# G1000_Cessna_Main.net
KiCad netlist of a schematic drawn in EasyEDA
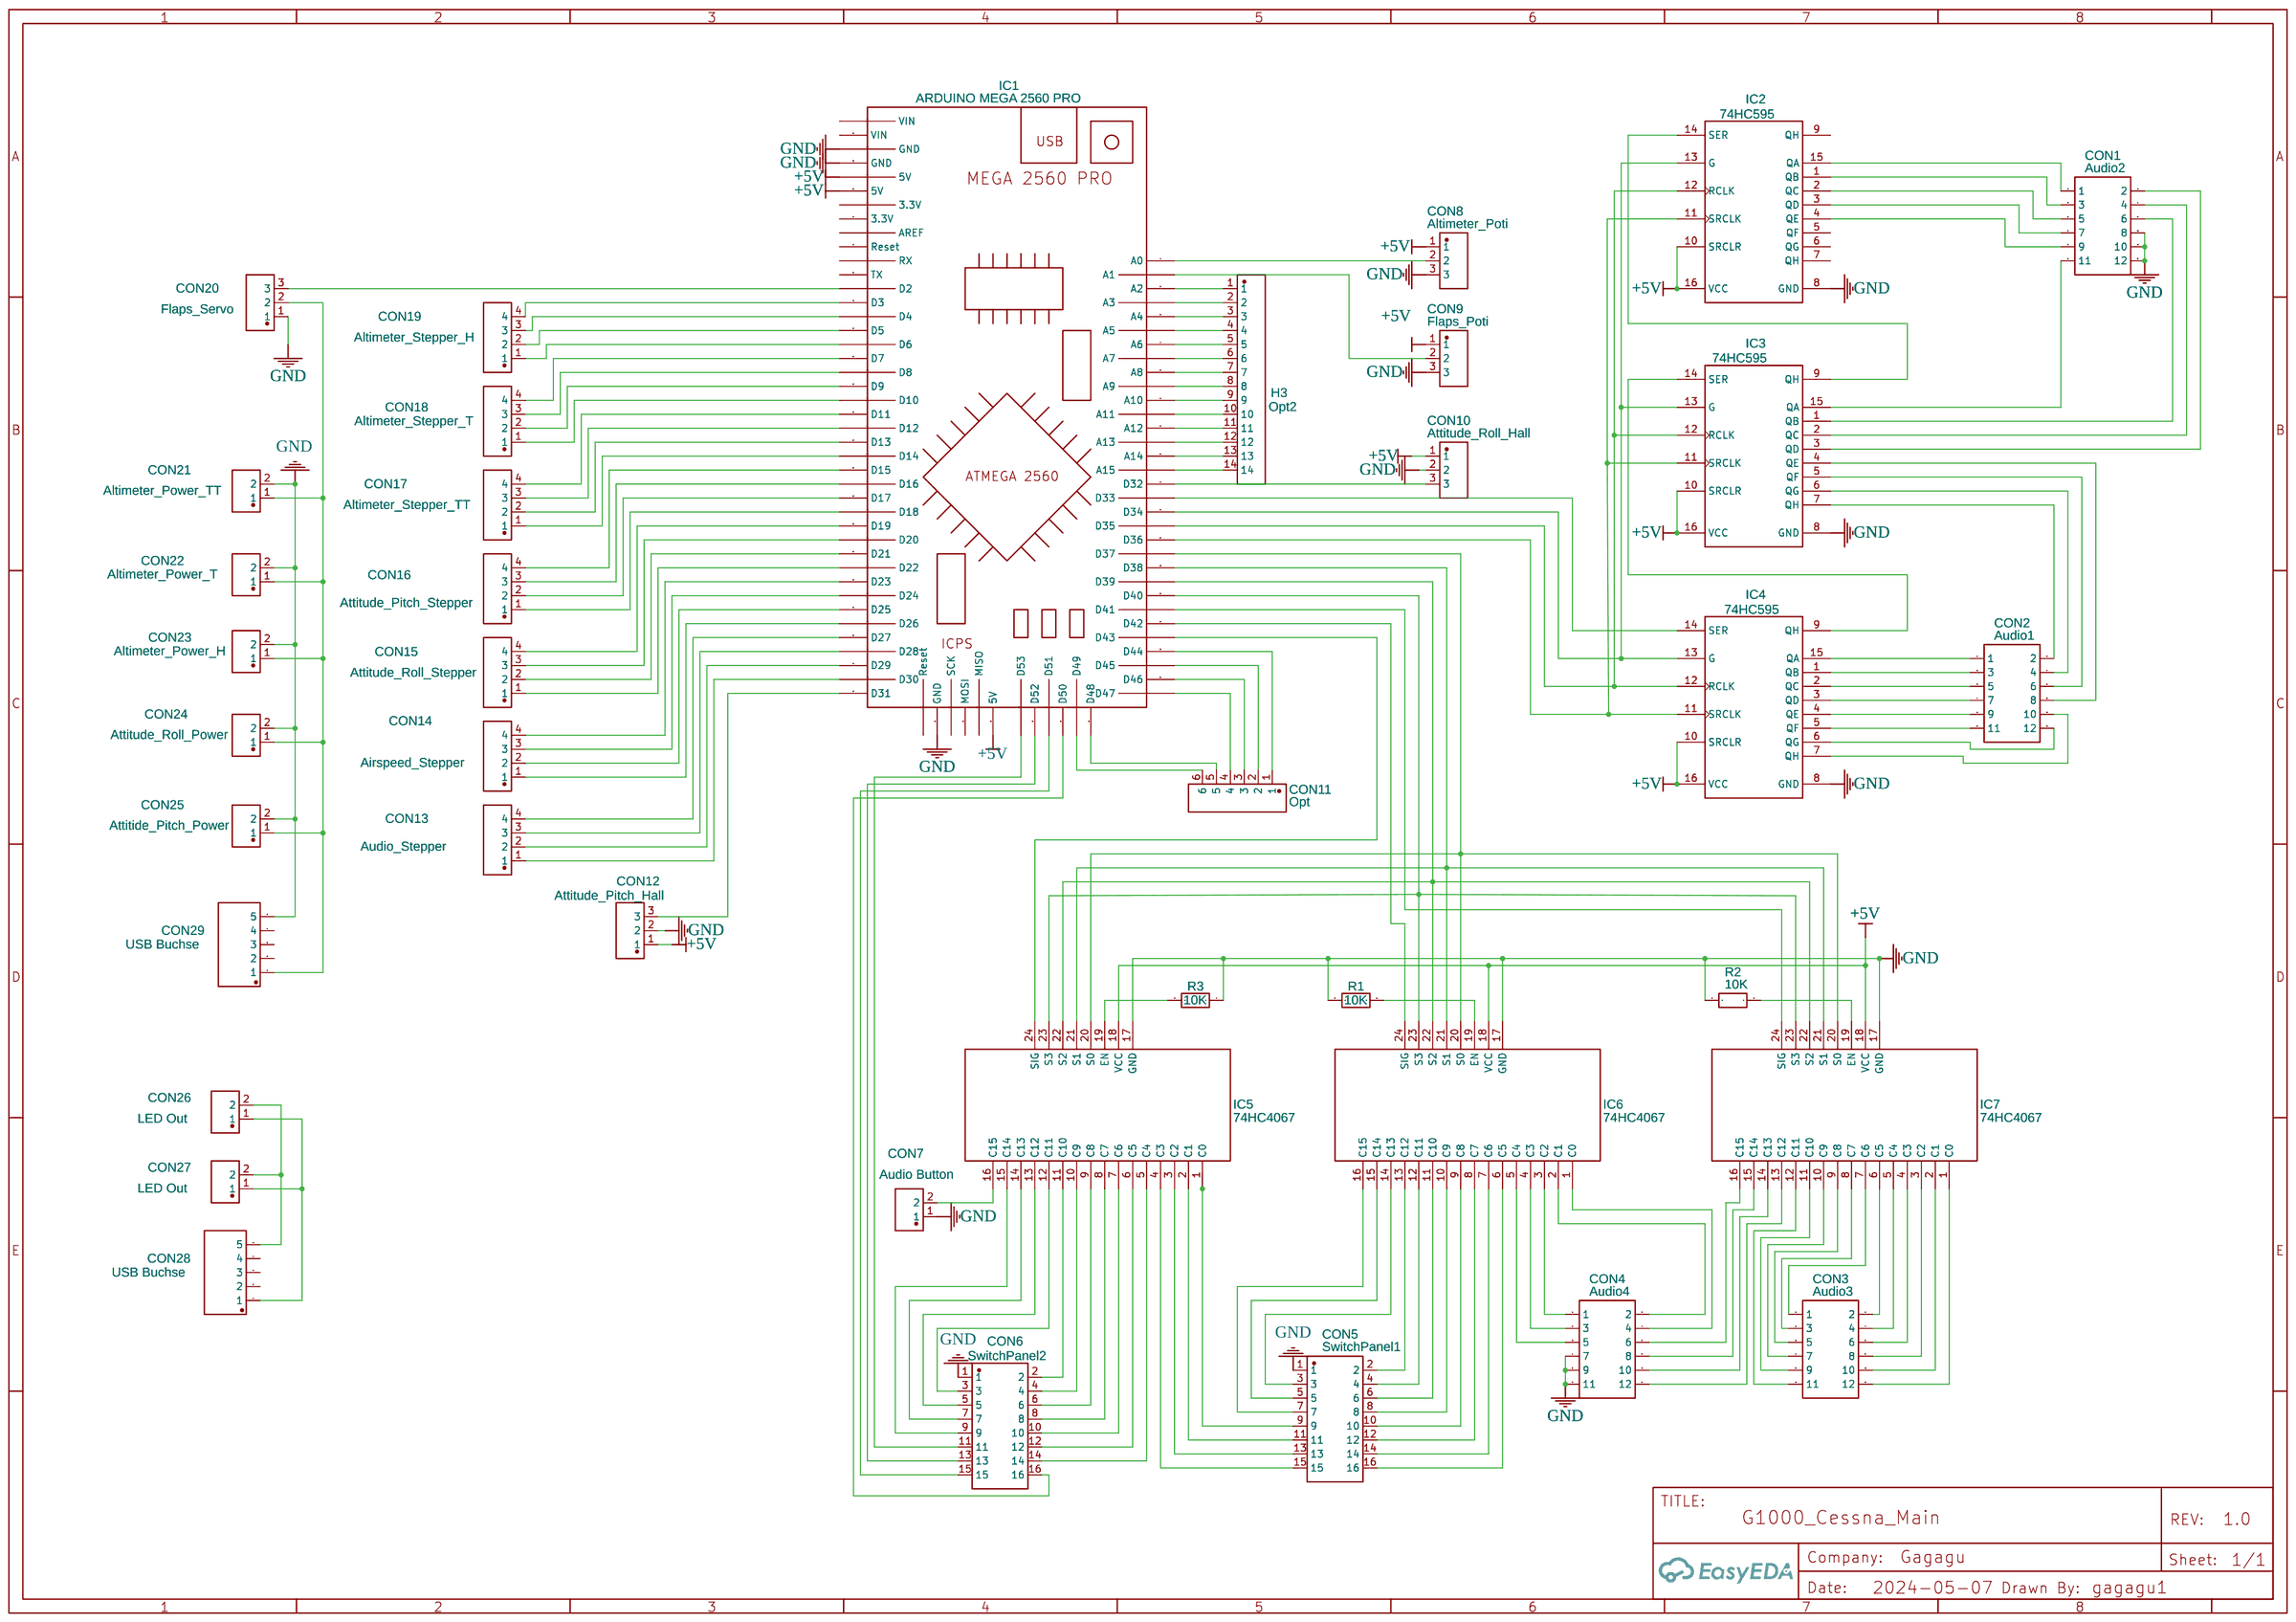
[diagram p0: schematic sheet]

(export (version "E")
  (design (tool "Eeschema 10.0.6"))
  (components
    (comp (ref "CON1")
      (value "Audio2")
      (fields (field (name "Manufacturer Part") "2.54-2*6P简牛") (field (name "Manufacturer") "BOOMELE(博穆精密)"))
      (libsource (lib "") (part "SOCKET HDR-IDC-2.54-2X6P"))
    )
    (comp (ref "CON2")
      (value "Audio1")
      (fields (field (name "Manufacturer Part") "2.54-2*6P简牛") (field (name "Manufacturer") "BOOMELE(博穆精密)"))
      (libsource (lib "") (part "SOCKET HDR-IDC-2.54-2X6P"))
    )
    (comp (ref "CON3")
      (value "Audio3")
      (fields (field (name "Manufacturer Part") "2.54-2*6P简牛") (field (name "Manufacturer") "BOOMELE(博穆精密)"))
      (libsource (lib "") (part "SOCKET HDR-IDC-2.54-2X6P"))
    )
    (comp (ref "CON4")
      (value "Audio4")
      (fields (field (name "Manufacturer Part") "2.54-2*6P简牛") (field (name "Manufacturer") "BOOMELE(博穆精密)"))
      (libsource (lib "") (part "SOCKET HDR-IDC-2.54-2X6P"))
    )
    (comp (ref "CON5")
      (value "SwitchPanel1")
      (fields
        (field (name "Manufacturer Part") "KH-2.54PH180-2X8P-L8.9")
        (field (name "Manufacturer") "kinghelm(金航标)")
      )
      (libsource (lib "") (part "KH-2.54PH180-2X8P-L8.9"))
    )
    (comp (ref "CON6")
      (value "SwitchPanel2")
      (fields
        (field (name "Manufacturer Part") "KH-2.54PH180-2X8P-L8.9")
        (field (name "Manufacturer") "kinghelm(金航标)")
      )
      (libsource (lib "") (part "KH-2.54PH180-2X8P-L8.9"))
    )
    (comp (ref "CON7")
      (value "Audio Button")
      (fields (field (name "Manufacturer Part") "HC-XH-2A-G") (field (name "Manufacturer") "HCTL(华灿天禄)"))
      (libsource (lib "") (part "HC-XH-2A-G"))
    )
    (comp (ref "CON8")
      (value "Altimeter_Poti")
      (fields (field (name "Manufacturer Part") "HC-XH-3A-G") (field (name "Manufacturer") "HCTL(华灿天禄)"))
      (libsource (lib "") (part "HC-XH-3A-G"))
    )
    (comp (ref "CON9")
      (value "Flaps_Poti")
      (fields (field (name "Manufacturer Part") "HC-XH-3A-G") (field (name "Manufacturer") "HCTL(华灿天禄)"))
      (libsource (lib "") (part "HC-XH-3A-G"))
    )
    (comp (ref "CON10")
      (value "Attitude_Roll_Hall")
      (fields (field (name "Manufacturer Part") "HC-XH-3A-G") (field (name "Manufacturer") "HCTL(华灿天禄)"))
      (libsource (lib "") (part "HC-XH-3A-G"))
    )
    (comp (ref "CON11")
      (value "Opt")
      (fields (field (name "Manufacturer Part") "XH-6A") (field (name "Manufacturer") "CAX"))
      (libsource (lib "") (part "ARUN-CONN-TH_XH-6A"))
    )
    (comp (ref "CON12")
      (value "Attitude_Pitch_Hall")
      (fields (field (name "Manufacturer Part") "HC-XH-3A-G") (field (name "Manufacturer") "HCTL(华灿天禄)"))
      (libsource (lib "") (part "HC-XH-3A-G_1"))
    )
    (comp (ref "CON13")
      (value "Audio_Stepper")
      (fields (field (name "Manufacturer Part") "XH-4A绿色") (field (name "Manufacturer") "BOOMELE(博穆精密)"))
      (libsource (lib "") (part "ARUN-CONN-TH_XH-4A"))
    )
    (comp (ref "CON14")
      (value "Airspeed_Stepper")
      (fields (field (name "Manufacturer Part") "XH-4A绿色") (field (name "Manufacturer") "BOOMELE(博穆精密)"))
      (libsource (lib "") (part "ARUN-CONN-TH_XH-4A"))
    )
    (comp (ref "CON15")
      (value "Attitude_Roll_Stepper")
      (fields (field (name "Manufacturer Part") "XH-4A绿色") (field (name "Manufacturer") "BOOMELE(博穆精密)"))
      (libsource (lib "") (part "ARUN-CONN-TH_XH-4A"))
    )
    (comp (ref "CON16")
      (value "Attitude_Pitch_Stepper")
      (fields (field (name "Manufacturer Part") "XH-4A绿色") (field (name "Manufacturer") "BOOMELE(博穆精密)"))
      (libsource (lib "") (part "ARUN-CONN-TH_XH-4A"))
    )
    (comp (ref "CON17")
      (value "Altimeter_Stepper_TT")
      (fields (field (name "Manufacturer Part") "XH-4A绿色") (field (name "Manufacturer") "BOOMELE(博穆精密)"))
      (libsource (lib "") (part "ARUN-CONN-TH_XH-4A"))
    )
    (comp (ref "CON18")
      (value "Altimeter_Stepper_T")
      (fields (field (name "Manufacturer Part") "XH-4A绿色") (field (name "Manufacturer") "BOOMELE(博穆精密)"))
      (libsource (lib "") (part "ARUN-CONN-TH_XH-4A"))
    )
    (comp (ref "CON19")
      (value "Altimeter_Stepper_H")
      (fields (field (name "Manufacturer Part") "XH-4A绿色") (field (name "Manufacturer") "BOOMELE(博穆精密)"))
      (libsource (lib "") (part "ARUN-CONN-TH_XH-4A"))
    )
    (comp (ref "CON20")
      (value "Flaps_Servo")
      (fields (field (name "Manufacturer Part") "HC-XH-3A-G") (field (name "Manufacturer") "HCTL(华灿天禄)"))
      (libsource (lib "") (part "HC-XH-3A-G_1"))
    )
    (comp (ref "CON21")
      (value "Altimeter_Power_TT")
      (fields (field (name "Manufacturer Part") "HC-XH-2A-G") (field (name "Manufacturer") "HCTL(华灿天禄)"))
      (libsource (lib "") (part "HC-XH-2A-G"))
    )
    (comp (ref "CON22")
      (value "Altimeter_Power_T")
      (fields (field (name "Manufacturer Part") "HC-XH-2A-G") (field (name "Manufacturer") "HCTL(华灿天禄)"))
      (libsource (lib "") (part "HC-XH-2A-G"))
    )
    (comp (ref "CON23")
      (value "Altimeter_Power_H")
      (fields (field (name "Manufacturer Part") "HC-XH-2A-G") (field (name "Manufacturer") "HCTL(华灿天禄)"))
      (libsource (lib "") (part "HC-XH-2A-G"))
    )
    (comp (ref "CON24")
      (value "Attitude_Roll_Power")
      (fields (field (name "Manufacturer Part") "HC-XH-2A-G") (field (name "Manufacturer") "HCTL(华灿天禄)"))
      (libsource (lib "") (part "HC-XH-2A-G"))
    )
    (comp (ref "CON25")
      (value "Attitide_Pitch_Power")
      (fields (field (name "Manufacturer Part") "HC-XH-2A-G") (field (name "Manufacturer") "HCTL(华灿天禄)"))
      (libsource (lib "") (part "HC-XH-2A-G"))
    )
    (comp (ref "CON26")
      (value "LED Out")
      (fields (field (name "Manufacturer Part") "HC-XH-2A-G") (field (name "Manufacturer") "HCTL(华灿天禄)"))
      (libsource (lib "") (part "HC-XH-2A-G"))
    )
    (comp (ref "CON27")
      (value "LED Out")
      (fields (field (name "Manufacturer Part") "HC-XH-2A-G") (field (name "Manufacturer") "HCTL(华灿天禄)"))
      (libsource (lib "") (part "HC-XH-2A-G"))
    )
    (comp (ref "CON28")
      (value "USB Buchse")
      (fields
        (field (name "Manufacturer Part") "210S-1*5P L=11.6MMGold-plated black")
        (field (name "Manufacturer") "Ckmtw")
      )
      (libsource (lib "") (part "Battery Pack Connector"))
    )
    (comp (ref "CON29")
      (value "USB Buchse")
      (fields
        (field (name "Manufacturer Part") "210S-1*5P L=11.6MMGold-plated black")
        (field (name "Manufacturer") "Ckmtw")
      )
      (libsource (lib "") (part "Battery Pack Connector"))
    )
    (comp (ref "H3")
      (value "Opt2")
      (fields
        (field (name "Manufacturer Part") "KH-1.27PH180-1X14P-L7.2")
        (field (name "Manufacturer") "kinghelm(金航标)")
      )
      (libsource (lib "") (part "KH-1.27PH180-1X14P-L7.2"))
    )
    (comp (ref "IC1")
      (value "ARDUINO MEGA 2560 PRO")
      (fields (field (name "Manufacturer Part") "Arduino Mega 2560 Pro Mini"))
      (libsource (lib "") (part "ARDUINO MEGA 2560 PRO_2020"))
    )
    (comp (ref "IC2") (value "74HC595") (libsource (lib "") (part "SN74HC595N_DIP")))
    (comp (ref "IC3") (value "74HC595") (libsource (lib "") (part "SN74HC595N_DIP")))
    (comp (ref "IC4") (value "74HC595") (libsource (lib "") (part "SN74HC595N_DIP")))
    (comp (ref "IC5") (value "74HC4067") (libsource (lib "") (part "CD74HC4067")))
    (comp (ref "IC6") (value "74HC4067") (libsource (lib "") (part "CD74HC4067")))
    (comp (ref "IC7") (value "74HC4067") (libsource (lib "") (part "CD74HC4067")))
    (comp (ref "R1") (value "10K") (libsource (lib "") (part "R_AXIAL-0.4_EU")))
    (comp (ref "R2") (value "10K") (libsource (lib "") (part "R_AXIAL-0.4_EU_1")))
    (comp (ref "R3") (value "10K") (libsource (lib "") (part "R_AXIAL-0.4_EU")))
  )
  (nets
    (net (code "1") (name "+5V") (class "Default")
      (node (ref "CON10") (pin "1") (pinfunction "1_1") (pintype "unspecified"))
      (node (ref "CON12") (pin "1") (pinfunction "1_1") (pintype "unspecified"))
      (node (ref "CON8") (pin "1") (pinfunction "1_1") (pintype "unspecified"))
      (node (ref "CON9") (pin "1") (pinfunction "1_1") (pintype "unspecified"))
      (node (ref "IC1") (pin "39") (pinfunction "5V_39") (pintype "unspecified"))
      (node (ref "IC1") (pin "81") (pinfunction "5V_81") (pintype "unspecified"))
      (node (ref "IC1") (pin "82") (pinfunction "5V_82") (pintype "unspecified"))
      (node (ref "IC2") (pin "10") (pinfunction "SRCLR_10") (pintype "unspecified"))
      (node (ref "IC2") (pin "16") (pinfunction "VCC_16") (pintype "passive"))
      (node (ref "IC3") (pin "10") (pinfunction "SRCLR_10") (pintype "unspecified"))
      (node (ref "IC3") (pin "16") (pinfunction "VCC_16") (pintype "passive"))
      (node (ref "IC4") (pin "10") (pinfunction "SRCLR_10") (pintype "unspecified"))
      (node (ref "IC4") (pin "16") (pinfunction "VCC_16") (pintype "passive"))
      (node (ref "IC5") (pin "18") (pinfunction "VCC_18") (pintype "unspecified"))
      (node (ref "IC6") (pin "18") (pinfunction "VCC_18") (pintype "unspecified"))
      (node (ref "IC7") (pin "18") (pinfunction "VCC_18") (pintype "unspecified"))
    )
    (net (code "2") (name "GND") (class "Default")
      (node (ref "CON1") (pin "10") (pinfunction "10_10") (pintype "unspecified"))
      (node (ref "CON1") (pin "12") (pinfunction "12_12") (pintype "unspecified"))
      (node (ref "CON1") (pin "8") (pinfunction "8_8") (pintype "unspecified"))
      (node (ref "CON10") (pin "2") (pinfunction "2_2") (pintype "unspecified"))
      (node (ref "CON12") (pin "2") (pinfunction "2_2") (pintype "unspecified"))
      (node (ref "CON20") (pin "1") (pinfunction "1_1") (pintype "unspecified"))
      (node (ref "CON21") (pin "2") (pinfunction "2_2") (pintype "unspecified"))
      (node (ref "CON22") (pin "2") (pinfunction "2_2") (pintype "unspecified"))
      (node (ref "CON23") (pin "2") (pinfunction "2_2") (pintype "unspecified"))
      (node (ref "CON24") (pin "2") (pinfunction "2_2") (pintype "unspecified"))
      (node (ref "CON25") (pin "2") (pinfunction "2_2") (pintype "unspecified"))
      (node (ref "CON29") (pin "5") (pinfunction "5_5") (pintype "unspecified"))
      (node (ref "CON4") (pin "11") (pinfunction "11_11") (pintype "unspecified"))
      (node (ref "CON4") (pin "7") (pinfunction "7_7") (pintype "unspecified"))
      (node (ref "CON4") (pin "9") (pinfunction "9_9") (pintype "unspecified"))
      (node (ref "CON5") (pin "1") (pinfunction "1_1") (pintype "unspecified"))
      (node (ref "CON6") (pin "1") (pinfunction "1_1") (pintype "unspecified"))
      (node (ref "CON7") (pin "1") (pinfunction "1_1") (pintype "unspecified"))
      (node (ref "CON8") (pin "3") (pinfunction "3_3") (pintype "unspecified"))
      (node (ref "CON9") (pin "3") (pinfunction "3_3") (pintype "unspecified"))
      (node (ref "IC1") (pin "43") (pinfunction "GND_43") (pintype "unspecified"))
      (node (ref "IC1") (pin "83") (pinfunction "GND_83") (pintype "unspecified"))
      (node (ref "IC1") (pin "84") (pinfunction "GND_84") (pintype "unspecified"))
      (node (ref "IC2") (pin "8") (pinfunction "GND_8") (pintype "passive"))
      (node (ref "IC3") (pin "8") (pinfunction "GND_8") (pintype "passive"))
      (node (ref "IC4") (pin "8") (pinfunction "GND_8") (pintype "passive"))
      (node (ref "IC5") (pin "17") (pinfunction "GND_17") (pintype "unspecified"))
      (node (ref "IC6") (pin "17") (pinfunction "GND_17") (pintype "unspecified"))
      (node (ref "IC7") (pin "17") (pinfunction "GND_17") (pintype "unspecified"))
      (node (ref "R1") (pin "2") (pinfunction "2_2") (pintype "unspecified"))
      (node (ref "R2") (pin "1") (pinfunction "1_1") (pintype "unspecified"))
      (node (ref "R3") (pin "1") (pinfunction "1_1") (pintype "unspecified"))
    )
    (net (code "3") (name "Net-(CON2-Pad2)") (class "Default")
      (node (ref "CON2") (pin "2") (pinfunction "2_2") (pintype "unspecified"))
      (node (ref "IC3") (pin "7") (pinfunction "QH_7") (pintype "unspecified"))
    )
    (net (code "4") (name "Net-(CON2-Pad10)") (class "Default")
      (node (ref "CON2") (pin "10") (pinfunction "10_10") (pintype "unspecified"))
      (node (ref "IC4") (pin "7") (pinfunction "QH_7") (pintype "unspecified"))
    )
    (net (code "5") (name "Net-(CON20-Pad2)") (class "Default")
      (node (ref "CON20") (pin "2") (pinfunction "2_2") (pintype "unspecified"))
      (node (ref "CON21") (pin "1") (pinfunction "1_1") (pintype "unspecified"))
      (node (ref "CON22") (pin "1") (pinfunction "1_1") (pintype "unspecified"))
      (node (ref "CON23") (pin "1") (pinfunction "1_1") (pintype "unspecified"))
      (node (ref "CON24") (pin "1") (pinfunction "1_1") (pintype "unspecified"))
      (node (ref "CON25") (pin "1") (pinfunction "1_1") (pintype "unspecified"))
      (node (ref "CON29") (pin "1") (pinfunction "1_1") (pintype "unspecified"))
    )
    (net (code "6") (name "Net-(CON26-Pad1)") (class "Default")
      (node (ref "CON26") (pin "1") (pinfunction "1_1") (pintype "unspecified"))
      (node (ref "CON27") (pin "1") (pinfunction "1_1") (pintype "unspecified"))
      (node (ref "CON28") (pin "1") (pinfunction "1_1") (pintype "unspecified"))
    )
    (net (code "7") (name "Net-(CON26-Pad2)") (class "Default")
      (node (ref "CON26") (pin "2") (pinfunction "2_2") (pintype "unspecified"))
      (node (ref "CON27") (pin "2") (pinfunction "2_2") (pintype "unspecified"))
      (node (ref "CON28") (pin "5") (pinfunction "5_5") (pintype "unspecified"))
    )
    (net (code "8") (name "Net-(IC1-A0)") (class "Default")
      (node (ref "CON8") (pin "2") (pinfunction "2_2") (pintype "unspecified"))
      (node (ref "IC1") (pin "1") (pinfunction "A0_1") (pintype "unspecified"))
    )
    (net (code "9") (name "Net-(IC1-A1)") (class "Default")
      (node (ref "CON9") (pin "2") (pinfunction "2_2") (pintype "unspecified"))
      (node (ref "IC1") (pin "2") (pinfunction "A1_2") (pintype "unspecified"))
    )
    (net (code "10") (name "Net-(IC1-A2)") (class "Default")
      (node (ref "H3") (pin "1") (pinfunction "1_1") (pintype "unspecified"))
      (node (ref "IC1") (pin "3") (pinfunction "A2_3") (pintype "unspecified"))
    )
    (net (code "11") (name "Net-(IC1-A3)") (class "Default")
      (node (ref "H3") (pin "2") (pinfunction "2_2") (pintype "unspecified"))
      (node (ref "IC1") (pin "4") (pinfunction "A3_4") (pintype "unspecified"))
    )
    (net (code "12") (name "Net-(IC1-A4)") (class "Default")
      (node (ref "H3") (pin "3") (pinfunction "3_3") (pintype "unspecified"))
      (node (ref "IC1") (pin "5") (pinfunction "A4_5") (pintype "unspecified"))
    )
    (net (code "13") (name "Net-(IC1-A5)") (class "Default")
      (node (ref "H3") (pin "4") (pinfunction "4_4") (pintype "unspecified"))
      (node (ref "IC1") (pin "6") (pinfunction "A5_6") (pintype "unspecified"))
    )
    (net (code "14") (name "Net-(IC1-A6)") (class "Default")
      (node (ref "H3") (pin "5") (pinfunction "5_5") (pintype "unspecified"))
      (node (ref "IC1") (pin "7") (pinfunction "A6_7") (pintype "unspecified"))
    )
    (net (code "15") (name "Net-(IC1-A7)") (class "Default")
      (node (ref "H3") (pin "6") (pinfunction "6_6") (pintype "unspecified"))
      (node (ref "IC1") (pin "8") (pinfunction "A7_8") (pintype "unspecified"))
    )
    (net (code "16") (name "Net-(IC1-A8)") (class "Default")
      (node (ref "H3") (pin "7") (pinfunction "7_7") (pintype "unspecified"))
      (node (ref "IC1") (pin "9") (pinfunction "A8_9") (pintype "unspecified"))
    )
    (net (code "17") (name "Net-(IC1-A9)") (class "Default")
      (node (ref "H3") (pin "8") (pinfunction "8_8") (pintype "unspecified"))
      (node (ref "IC1") (pin "10") (pinfunction "A9_10") (pintype "unspecified"))
    )
    (net (code "18") (name "Net-(IC1-A10)") (class "Default")
      (node (ref "H3") (pin "9") (pinfunction "9_9") (pintype "unspecified"))
      (node (ref "IC1") (pin "11") (pinfunction "A10_11") (pintype "unspecified"))
    )
    (net (code "19") (name "Net-(IC1-A11)") (class "Default")
      (node (ref "H3") (pin "10") (pinfunction "10_10") (pintype "unspecified"))
      (node (ref "IC1") (pin "12") (pinfunction "A11_12") (pintype "unspecified"))
    )
    (net (code "20") (name "Net-(IC1-A12)") (class "Default")
      (node (ref "H3") (pin "11") (pinfunction "11_11") (pintype "unspecified"))
      (node (ref "IC1") (pin "13") (pinfunction "A12_13") (pintype "unspecified"))
    )
    (net (code "21") (name "Net-(IC1-A13)") (class "Default")
      (node (ref "H3") (pin "12") (pinfunction "12_12") (pintype "unspecified"))
      (node (ref "IC1") (pin "14") (pinfunction "A13_14") (pintype "unspecified"))
    )
    (net (code "22") (name "Net-(IC1-A14)") (class "Default")
      (node (ref "H3") (pin "13") (pinfunction "13_13") (pintype "unspecified"))
      (node (ref "IC1") (pin "15") (pinfunction "A14_15") (pintype "unspecified"))
    )
    (net (code "23") (name "Net-(IC1-A15)") (class "Default")
      (node (ref "H3") (pin "14") (pinfunction "14_14") (pintype "unspecified"))
      (node (ref "IC1") (pin "16") (pinfunction "A15_16") (pintype "unspecified"))
    )
    (net (code "24") (name "Net-(IC1-D2)") (class "Default")
      (node (ref "CON20") (pin "3") (pinfunction "3_3") (pintype "unspecified"))
      (node (ref "IC1") (pin "74") (pinfunction "D2_74") (pintype "unspecified"))
    )
    (net (code "25") (name "Net-(IC1-D3)") (class "Default")
      (node (ref "CON19") (pin "4") (pinfunction "4_4") (pintype "unspecified"))
      (node (ref "IC1") (pin "73") (pinfunction "D3_73") (pintype "unspecified"))
    )
    (net (code "26") (name "Net-(IC1-D4)") (class "Default")
      (node (ref "CON19") (pin "3") (pinfunction "3_3") (pintype "unspecified"))
      (node (ref "IC1") (pin "72") (pinfunction "D4_72") (pintype "unspecified"))
    )
    (net (code "27") (name "Net-(IC1-D5)") (class "Default")
      (node (ref "CON19") (pin "2") (pinfunction "2_2") (pintype "unspecified"))
      (node (ref "IC1") (pin "71") (pinfunction "D5_71") (pintype "unspecified"))
    )
    (net (code "28") (name "Net-(IC1-D6)") (class "Default")
      (node (ref "CON19") (pin "1") (pinfunction "1_1") (pintype "unspecified"))
      (node (ref "IC1") (pin "70") (pinfunction "D6_70") (pintype "unspecified"))
    )
    (net (code "29") (name "Net-(IC1-D7)") (class "Default")
      (node (ref "CON18") (pin "4") (pinfunction "4_4") (pintype "unspecified"))
      (node (ref "IC1") (pin "69") (pinfunction "D7_69") (pintype "unspecified"))
    )
    (net (code "30") (name "Net-(IC1-D8)") (class "Default")
      (node (ref "CON18") (pin "3") (pinfunction "3_3") (pintype "unspecified"))
      (node (ref "IC1") (pin "68") (pinfunction "D8_68") (pintype "unspecified"))
    )
    (net (code "31") (name "Net-(IC1-D9)") (class "Default")
      (node (ref "CON18") (pin "2") (pinfunction "2_2") (pintype "unspecified"))
      (node (ref "IC1") (pin "67") (pinfunction "D9_67") (pintype "unspecified"))
    )
    (net (code "32") (name "Net-(IC1-D10)") (class "Default")
      (node (ref "CON18") (pin "1") (pinfunction "1_1") (pintype "unspecified"))
      (node (ref "IC1") (pin "66") (pinfunction "D10_66") (pintype "unspecified"))
    )
    (net (code "33") (name "Net-(IC1-D11)") (class "Default")
      (node (ref "CON17") (pin "4") (pinfunction "4_4") (pintype "unspecified"))
      (node (ref "IC1") (pin "65") (pinfunction "D11_65") (pintype "unspecified"))
    )
    (net (code "34") (name "Net-(IC1-D12)") (class "Default")
      (node (ref "CON17") (pin "3") (pinfunction "3_3") (pintype "unspecified"))
      (node (ref "IC1") (pin "64") (pinfunction "D12_64") (pintype "unspecified"))
    )
    (net (code "35") (name "Net-(IC1-D13)") (class "Default")
      (node (ref "CON17") (pin "2") (pinfunction "2_2") (pintype "unspecified"))
      (node (ref "IC1") (pin "63") (pinfunction "D13_63") (pintype "unspecified"))
    )
    (net (code "36") (name "Net-(IC1-D14)") (class "Default")
      (node (ref "CON17") (pin "1") (pinfunction "1_1") (pintype "unspecified"))
      (node (ref "IC1") (pin "62") (pinfunction "D14_62") (pintype "unspecified"))
    )
    (net (code "37") (name "Net-(IC1-D15)") (class "Default")
      (node (ref "CON16") (pin "4") (pinfunction "4_4") (pintype "unspecified"))
      (node (ref "IC1") (pin "61") (pinfunction "D15_61") (pintype "unspecified"))
    )
    (net (code "38") (name "Net-(IC1-D16)") (class "Default")
      (node (ref "CON16") (pin "3") (pinfunction "3_3") (pintype "unspecified"))
      (node (ref "IC1") (pin "60") (pinfunction "D16_60") (pintype "unspecified"))
    )
    (net (code "39") (name "Net-(IC1-D17)") (class "Default")
      (node (ref "CON16") (pin "2") (pinfunction "2_2") (pintype "unspecified"))
      (node (ref "IC1") (pin "59") (pinfunction "D17_59") (pintype "unspecified"))
    )
    (net (code "40") (name "Net-(IC1-D18)") (class "Default")
      (node (ref "CON16") (pin "1") (pinfunction "1_1") (pintype "unspecified"))
      (node (ref "IC1") (pin "58") (pinfunction "D18_58") (pintype "unspecified"))
    )
    (net (code "41") (name "Net-(IC1-D19)") (class "Default")
      (node (ref "CON15") (pin "4") (pinfunction "4_4") (pintype "unspecified"))
      (node (ref "IC1") (pin "57") (pinfunction "D19_57") (pintype "unspecified"))
    )
    (net (code "42") (name "Net-(IC1-D20)") (class "Default")
      (node (ref "CON15") (pin "3") (pinfunction "3_3") (pintype "unspecified"))
      (node (ref "IC1") (pin "56") (pinfunction "D20_56") (pintype "unspecified"))
    )
    (net (code "43") (name "Net-(IC1-D21)") (class "Default")
      (node (ref "CON15") (pin "2") (pinfunction "2_2") (pintype "unspecified"))
      (node (ref "IC1") (pin "55") (pinfunction "D21_55") (pintype "unspecified"))
    )
    (net (code "44") (name "Net-(IC1-D22)") (class "Default")
      (node (ref "CON15") (pin "1") (pinfunction "1_1") (pintype "unspecified"))
      (node (ref "IC1") (pin "54") (pinfunction "D22_54") (pintype "unspecified"))
    )
    (net (code "45") (name "Net-(IC1-D23)") (class "Default")
      (node (ref "CON14") (pin "4") (pinfunction "4_4") (pintype "unspecified"))
      (node (ref "IC1") (pin "53") (pinfunction "D23_53") (pintype "unspecified"))
    )
    (net (code "46") (name "Net-(IC1-D24)") (class "Default")
      (node (ref "CON14") (pin "3") (pinfunction "3_3") (pintype "unspecified"))
      (node (ref "IC1") (pin "52") (pinfunction "D24_52") (pintype "unspecified"))
    )
    (net (code "47") (name "Net-(IC1-D25)") (class "Default")
      (node (ref "CON14") (pin "2") (pinfunction "2_2") (pintype "unspecified"))
      (node (ref "IC1") (pin "51") (pinfunction "D25_51") (pintype "unspecified"))
    )
    (net (code "48") (name "Net-(IC1-D26)") (class "Default")
      (node (ref "CON14") (pin "1") (pinfunction "1_1") (pintype "unspecified"))
      (node (ref "IC1") (pin "50") (pinfunction "D26_50") (pintype "unspecified"))
    )
    (net (code "49") (name "Net-(IC1-D27)") (class "Default")
      (node (ref "CON13") (pin "4") (pinfunction "4_4") (pintype "unspecified"))
      (node (ref "IC1") (pin "49") (pinfunction "D27_49") (pintype "unspecified"))
    )
    (net (code "50") (name "Net-(IC1-D28)") (class "Default")
      (node (ref "CON13") (pin "3") (pinfunction "3_3") (pintype "unspecified"))
      (node (ref "IC1") (pin "48") (pinfunction "D28_48") (pintype "unspecified"))
    )
    (net (code "51") (name "Net-(IC1-D29)") (class "Default")
      (node (ref "CON13") (pin "2") (pinfunction "2_2") (pintype "unspecified"))
      (node (ref "IC1") (pin "47") (pinfunction "D29_47") (pintype "unspecified"))
    )
    (net (code "52") (name "Net-(IC1-D30)") (class "Default")
      (node (ref "CON13") (pin "1") (pinfunction "1_1") (pintype "unspecified"))
      (node (ref "IC1") (pin "46") (pinfunction "D30_46") (pintype "unspecified"))
    )
    (net (code "53") (name "Net-(IC1-D31)") (class "Default")
      (node (ref "CON12") (pin "3") (pinfunction "3_3") (pintype "unspecified"))
      (node (ref "IC1") (pin "45") (pinfunction "D31_45") (pintype "unspecified"))
    )
    (net (code "54") (name "Net-(IC1-D32)") (class "Default")
      (node (ref "CON10") (pin "3") (pinfunction "3_3") (pintype "unspecified"))
      (node (ref "IC1") (pin "17") (pinfunction "D32_17") (pintype "unspecified"))
    )
    (net (code "55") (name "Net-(IC1-D33)") (class "Default")
      (node (ref "IC1") (pin "18") (pinfunction "D33_18") (pintype "unspecified"))
      (node (ref "IC4") (pin "14") (pinfunction "SER_14") (pintype "unspecified"))
    )
    (net (code "56") (name "Net-(IC1-D34)") (class "Default")
      (node (ref "IC1") (pin "19") (pinfunction "D34_19") (pintype "unspecified"))
      (node (ref "IC2") (pin "13") (pinfunction "G_13") (pintype "unspecified"))
      (node (ref "IC3") (pin "13") (pinfunction "G_13") (pintype "unspecified"))
      (node (ref "IC4") (pin "13") (pinfunction "G_13") (pintype "unspecified"))
    )
    (net (code "57") (name "Net-(IC1-D35)") (class "Default")
      (node (ref "IC1") (pin "20") (pinfunction "D35_20") (pintype "unspecified"))
      (node (ref "IC2") (pin "12") (pinfunction "RCLK_12") (pintype "unspecified"))
      (node (ref "IC3") (pin "12") (pinfunction "RCLK_12") (pintype "unspecified"))
      (node (ref "IC4") (pin "12") (pinfunction "RCLK_12") (pintype "unspecified"))
    )
    (net (code "58") (name "Net-(IC1-D36)") (class "Default")
      (node (ref "IC1") (pin "21") (pinfunction "D36_21") (pintype "unspecified"))
      (node (ref "IC2") (pin "11") (pinfunction "SRCLK_11") (pintype "unspecified"))
      (node (ref "IC3") (pin "11") (pinfunction "SRCLK_11") (pintype "unspecified"))
      (node (ref "IC4") (pin "11") (pinfunction "SRCLK_11") (pintype "unspecified"))
    )
    (net (code "59") (name "Net-(IC1-D37)") (class "Default")
      (node (ref "IC1") (pin "22") (pinfunction "D37_22") (pintype "unspecified"))
      (node (ref "IC5") (pin "20") (pinfunction "S0_20") (pintype "unspecified"))
      (node (ref "IC6") (pin "20") (pinfunction "S0_20") (pintype "unspecified"))
      (node (ref "IC7") (pin "20") (pinfunction "S0_20") (pintype "unspecified"))
    )
    (net (code "60") (name "Net-(IC1-D38)") (class "Default")
      (node (ref "IC1") (pin "23") (pinfunction "D38_23") (pintype "unspecified"))
      (node (ref "IC5") (pin "21") (pinfunction "S1_21") (pintype "unspecified"))
      (node (ref "IC6") (pin "21") (pinfunction "S1_21") (pintype "unspecified"))
      (node (ref "IC7") (pin "21") (pinfunction "S1_21") (pintype "unspecified"))
    )
    (net (code "61") (name "Net-(IC1-D39)") (class "Default")
      (node (ref "IC1") (pin "24") (pinfunction "D39_24") (pintype "unspecified"))
      (node (ref "IC5") (pin "22") (pinfunction "S2_22") (pintype "unspecified"))
      (node (ref "IC6") (pin "22") (pinfunction "S2_22") (pintype "unspecified"))
      (node (ref "IC7") (pin "22") (pinfunction "S2_22") (pintype "unspecified"))
    )
    (net (code "62") (name "Net-(IC1-D40)") (class "Default")
      (node (ref "IC1") (pin "25") (pinfunction "D40_25") (pintype "unspecified"))
      (node (ref "IC5") (pin "23") (pinfunction "S3_23") (pintype "unspecified"))
      (node (ref "IC6") (pin "23") (pinfunction "S3_23") (pintype "unspecified"))
      (node (ref "IC7") (pin "23") (pinfunction "S3_23") (pintype "unspecified"))
    )
    (net (code "63") (name "Net-(IC1-D41)") (class "Default")
      (node (ref "IC1") (pin "26") (pinfunction "D41_26") (pintype "unspecified"))
      (node (ref "IC7") (pin "24") (pinfunction "SIG_24") (pintype "unspecified"))
    )
    (net (code "64") (name "Net-(IC1-D42)") (class "Default")
      (node (ref "IC1") (pin "27") (pinfunction "D42_27") (pintype "unspecified"))
      (node (ref "IC6") (pin "24") (pinfunction "SIG_24") (pintype "unspecified"))
    )
    (net (code "65") (name "Net-(IC1-D43)") (class "Default")
      (node (ref "IC1") (pin "28") (pinfunction "D43_28") (pintype "unspecified"))
      (node (ref "IC5") (pin "24") (pinfunction "SIG_24") (pintype "unspecified"))
    )
    (net (code "66") (name "Net-(IC1-D44)") (class "Default")
      (node (ref "CON11") (pin "1") (pinfunction "1_1") (pintype "unspecified"))
      (node (ref "IC1") (pin "29") (pinfunction "D44_29") (pintype "unspecified"))
    )
    (net (code "67") (name "Net-(IC1-D45)") (class "Default")
      (node (ref "CON11") (pin "2") (pinfunction "2_2") (pintype "unspecified"))
      (node (ref "IC1") (pin "30") (pinfunction "D45_30") (pintype "unspecified"))
    )
    (net (code "68") (name "Net-(IC1-D46)") (class "Default")
      (node (ref "CON11") (pin "3") (pinfunction "3_3") (pintype "unspecified"))
      (node (ref "IC1") (pin "31") (pinfunction "D46_31") (pintype "unspecified"))
    )
    (net (code "69") (name "Net-(IC1-D47)") (class "Default")
      (node (ref "CON11") (pin "4") (pinfunction "4_4") (pintype "unspecified"))
      (node (ref "IC1") (pin "32") (pinfunction "D47_32") (pintype "unspecified"))
    )
    (net (code "70") (name "Net-(IC1-D48)") (class "Default")
      (node (ref "CON11") (pin "5") (pinfunction "5_5") (pintype "unspecified"))
      (node (ref "IC1") (pin "33") (pinfunction "D48_33") (pintype "unspecified"))
    )
    (net (code "71") (name "Net-(IC1-D49)") (class "Default")
      (node (ref "CON11") (pin "6") (pinfunction "6_6") (pintype "unspecified"))
      (node (ref "IC1") (pin "34") (pinfunction "D49_34") (pintype "unspecified"))
    )
    (net (code "72") (name "Net-(IC1-D50)") (class "Default")
      (node (ref "CON6") (pin "16") (pinfunction "16_16") (pintype "unspecified"))
      (node (ref "IC1") (pin "35") (pinfunction "D50_35") (pintype "unspecified"))
    )
    (net (code "73") (name "Net-(IC1-D51)") (class "Default")
      (node (ref "CON6") (pin "15") (pinfunction "15_15") (pintype "unspecified"))
      (node (ref "IC1") (pin "36") (pinfunction "D51_36") (pintype "unspecified"))
    )
    (net (code "74") (name "Net-(IC1-D52)") (class "Default")
      (node (ref "CON6") (pin "13") (pinfunction "13_13") (pintype "unspecified"))
      (node (ref "IC1") (pin "37") (pinfunction "D52_37") (pintype "unspecified"))
    )
    (net (code "75") (name "Net-(IC1-D53)") (class "Default")
      (node (ref "CON6") (pin "11") (pinfunction "11_11") (pintype "unspecified"))
      (node (ref "IC1") (pin "38") (pinfunction "D53_38") (pintype "unspecified"))
    )
    (net (code "76") (name "Net-(IC2-QA)") (class "Default")
      (node (ref "CON1") (pin "1") (pinfunction "1_1") (pintype "unspecified"))
      (node (ref "IC2") (pin "15") (pinfunction "QA_15") (pintype "unspecified"))
    )
    (net (code "77") (name "Net-(IC2-QB)") (class "Default")
      (node (ref "CON1") (pin "3") (pinfunction "3_3") (pintype "unspecified"))
      (node (ref "IC2") (pin "1") (pinfunction "QB_1") (pintype "unspecified"))
    )
    (net (code "78") (name "Net-(IC2-QC)") (class "Default")
      (node (ref "CON1") (pin "5") (pinfunction "5_5") (pintype "unspecified"))
      (node (ref "IC2") (pin "2") (pinfunction "QC_2") (pintype "unspecified"))
    )
    (net (code "79") (name "Net-(IC2-QD)") (class "Default")
      (node (ref "CON1") (pin "7") (pinfunction "7_7") (pintype "unspecified"))
      (node (ref "IC2") (pin "3") (pinfunction "QD_3") (pintype "unspecified"))
    )
    (net (code "80") (name "Net-(IC2-QE)") (class "Default")
      (node (ref "CON1") (pin "9") (pinfunction "9_9") (pintype "unspecified"))
      (node (ref "IC2") (pin "4") (pinfunction "QE_4") (pintype "unspecified"))
    )
    (net (code "81") (name "Net-(IC2-SER)") (class "Default")
      (node (ref "IC2") (pin "14") (pinfunction "SER_14") (pintype "unspecified"))
      (node (ref "IC3") (pin "9") (pinfunction "QH_9") (pintype "output"))
    )
    (net (code "82") (name "Net-(IC3-QA)") (class "Default")
      (node (ref "CON1") (pin "11") (pinfunction "11_11") (pintype "unspecified"))
      (node (ref "IC3") (pin "15") (pinfunction "QA_15") (pintype "unspecified"))
    )
    (net (code "83") (name "Net-(IC3-QB)") (class "Default")
      (node (ref "CON1") (pin "6") (pinfunction "6_6") (pintype "unspecified"))
      (node (ref "IC3") (pin "1") (pinfunction "QB_1") (pintype "unspecified"))
    )
    (net (code "84") (name "Net-(IC3-QC)") (class "Default")
      (node (ref "CON1") (pin "4") (pinfunction "4_4") (pintype "unspecified"))
      (node (ref "IC3") (pin "2") (pinfunction "QC_2") (pintype "unspecified"))
    )
    (net (code "85") (name "Net-(IC3-QD)") (class "Default")
      (node (ref "CON1") (pin "2") (pinfunction "2_2") (pintype "unspecified"))
      (node (ref "IC3") (pin "3") (pinfunction "QD_3") (pintype "unspecified"))
    )
    (net (code "86") (name "Net-(IC3-QE)") (class "Default")
      (node (ref "CON2") (pin "8") (pinfunction "8_8") (pintype "unspecified"))
      (node (ref "IC3") (pin "4") (pinfunction "QE_4") (pintype "unspecified"))
    )
    (net (code "87") (name "Net-(IC3-QF)") (class "Default")
      (node (ref "CON2") (pin "6") (pinfunction "6_6") (pintype "unspecified"))
      (node (ref "IC3") (pin "5") (pinfunction "QF_5") (pintype "unspecified"))
    )
    (net (code "88") (name "Net-(IC3-QG)") (class "Default")
      (node (ref "CON2") (pin "4") (pinfunction "4_4") (pintype "unspecified"))
      (node (ref "IC3") (pin "6") (pinfunction "QG_6") (pintype "unspecified"))
    )
    (net (code "89") (name "Net-(IC3-SER)") (class "Default")
      (node (ref "IC3") (pin "14") (pinfunction "SER_14") (pintype "unspecified"))
      (node (ref "IC4") (pin "9") (pinfunction "QH_9") (pintype "output"))
    )
    (net (code "90") (name "Net-(IC4-QA)") (class "Default")
      (node (ref "CON2") (pin "1") (pinfunction "1_1") (pintype "unspecified"))
      (node (ref "IC4") (pin "15") (pinfunction "QA_15") (pintype "unspecified"))
    )
    (net (code "91") (name "Net-(IC4-QB)") (class "Default")
      (node (ref "CON2") (pin "3") (pinfunction "3_3") (pintype "unspecified"))
      (node (ref "IC4") (pin "1") (pinfunction "QB_1") (pintype "unspecified"))
    )
    (net (code "92") (name "Net-(IC4-QC)") (class "Default")
      (node (ref "CON2") (pin "5") (pinfunction "5_5") (pintype "unspecified"))
      (node (ref "IC4") (pin "2") (pinfunction "QC_2") (pintype "unspecified"))
    )
    (net (code "93") (name "Net-(IC4-QD)") (class "Default")
      (node (ref "CON2") (pin "7") (pinfunction "7_7") (pintype "unspecified"))
      (node (ref "IC4") (pin "3") (pinfunction "QD_3") (pintype "unspecified"))
    )
    (net (code "94") (name "Net-(IC4-QE)") (class "Default")
      (node (ref "CON2") (pin "9") (pinfunction "9_9") (pintype "unspecified"))
      (node (ref "IC4") (pin "4") (pinfunction "QE_4") (pintype "unspecified"))
    )
    (net (code "95") (name "Net-(IC4-QF)") (class "Default")
      (node (ref "CON2") (pin "11") (pinfunction "11_11") (pintype "unspecified"))
      (node (ref "IC4") (pin "5") (pinfunction "QF_5") (pintype "unspecified"))
    )
    (net (code "96") (name "Net-(IC4-QG)") (class "Default")
      (node (ref "CON2") (pin "12") (pinfunction "12_12") (pintype "unspecified"))
      (node (ref "IC4") (pin "6") (pinfunction "QG_6") (pintype "unspecified"))
    )
    (net (code "97") (name "Net-(IC5-C0)") (class "Default")
      (node (ref "CON5") (pin "9") (pinfunction "9_9") (pintype "unspecified"))
      (node (ref "IC5") (pin "1") (pinfunction "C0_1") (pintype "unspecified"))
    )
    (net (code "98") (name "Net-(IC5-C1)") (class "Default")
      (node (ref "CON5") (pin "11") (pinfunction "11_11") (pintype "unspecified"))
      (node (ref "IC5") (pin "2") (pinfunction "C1_2") (pintype "unspecified"))
    )
    (net (code "99") (name "Net-(IC5-C2)") (class "Default")
      (node (ref "CON5") (pin "13") (pinfunction "13_13") (pintype "unspecified"))
      (node (ref "IC5") (pin "3") (pinfunction "C2_3") (pintype "unspecified"))
    )
    (net (code "100") (name "Net-(IC5-C3)") (class "Default")
      (node (ref "CON5") (pin "15") (pinfunction "15_15") (pintype "unspecified"))
      (node (ref "IC5") (pin "4") (pinfunction "C3_4") (pintype "unspecified"))
    )
    (net (code "101") (name "Net-(IC5-C4)") (class "Default")
      (node (ref "CON6") (pin "14") (pinfunction "14_14") (pintype "unspecified"))
      (node (ref "IC5") (pin "5") (pinfunction "C4_5") (pintype "unspecified"))
    )
    (net (code "102") (name "Net-(IC5-C5)") (class "Default")
      (node (ref "CON6") (pin "12") (pinfunction "12_12") (pintype "unspecified"))
      (node (ref "IC5") (pin "6") (pinfunction "C5_6") (pintype "unspecified"))
    )
    (net (code "103") (name "Net-(IC5-C6)") (class "Default")
      (node (ref "CON6") (pin "10") (pinfunction "10_10") (pintype "unspecified"))
      (node (ref "IC5") (pin "7") (pinfunction "C6_7") (pintype "unspecified"))
    )
    (net (code "104") (name "Net-(IC5-C7)") (class "Default")
      (node (ref "CON6") (pin "8") (pinfunction "8_8") (pintype "unspecified"))
      (node (ref "IC5") (pin "8") (pinfunction "C7_8") (pintype "unspecified"))
    )
    (net (code "105") (name "Net-(IC5-C8)") (class "Default")
      (node (ref "CON6") (pin "6") (pinfunction "6_6") (pintype "unspecified"))
      (node (ref "IC5") (pin "9") (pinfunction "C8_9") (pintype "unspecified"))
    )
    (net (code "106") (name "Net-(IC5-C9)") (class "Default")
      (node (ref "CON6") (pin "4") (pinfunction "4_4") (pintype "unspecified"))
      (node (ref "IC5") (pin "10") (pinfunction "C9_10") (pintype "unspecified"))
    )
    (net (code "107") (name "Net-(IC5-C10)") (class "Default")
      (node (ref "CON6") (pin "2") (pinfunction "2_2") (pintype "unspecified"))
      (node (ref "IC5") (pin "11") (pinfunction "C10_11") (pintype "unspecified"))
    )
    (net (code "108") (name "Net-(IC5-C11)") (class "Default")
      (node (ref "CON6") (pin "3") (pinfunction "3_3") (pintype "unspecified"))
      (node (ref "IC5") (pin "12") (pinfunction "C11_12") (pintype "unspecified"))
    )
    (net (code "109") (name "Net-(IC5-C12)") (class "Default")
      (node (ref "CON6") (pin "5") (pinfunction "5_5") (pintype "unspecified"))
      (node (ref "IC5") (pin "13") (pinfunction "C12_13") (pintype "unspecified"))
    )
    (net (code "110") (name "Net-(IC5-C13)") (class "Default")
      (node (ref "CON6") (pin "7") (pinfunction "7_7") (pintype "unspecified"))
      (node (ref "IC5") (pin "14") (pinfunction "C13_14") (pintype "unspecified"))
    )
    (net (code "111") (name "Net-(IC5-C14)") (class "Default")
      (node (ref "CON6") (pin "9") (pinfunction "9_9") (pintype "unspecified"))
      (node (ref "IC5") (pin "15") (pinfunction "C14_15") (pintype "unspecified"))
    )
    (net (code "112") (name "Net-(IC5-C15)") (class "Default")
      (node (ref "CON7") (pin "2") (pinfunction "2_2") (pintype "unspecified"))
      (node (ref "IC5") (pin "16") (pinfunction "C15_16") (pintype "unspecified"))
    )
    (net (code "113") (name "Net-(IC5-EN)") (class "Default")
      (node (ref "IC5") (pin "19") (pinfunction "EN_19") (pintype "unspecified"))
      (node (ref "R3") (pin "2") (pinfunction "2_2") (pintype "unspecified"))
    )
    (net (code "114") (name "Net-(IC6-C0)") (class "Default")
      (node (ref "CON4") (pin "4") (pinfunction "4_4") (pintype "unspecified"))
      (node (ref "IC6") (pin "1") (pinfunction "C0_1") (pintype "unspecified"))
    )
    (net (code "115") (name "Net-(IC6-C1)") (class "Default")
      (node (ref "CON4") (pin "2") (pinfunction "2_2") (pintype "unspecified"))
      (node (ref "IC6") (pin "2") (pinfunction "C1_2") (pintype "unspecified"))
    )
    (net (code "116") (name "Net-(IC6-C2)") (class "Default")
      (node (ref "CON4") (pin "1") (pinfunction "1_1") (pintype "unspecified"))
      (node (ref "IC6") (pin "3") (pinfunction "C2_3") (pintype "unspecified"))
    )
    (net (code "117") (name "Net-(IC6-C3)") (class "Default")
      (node (ref "CON4") (pin "3") (pinfunction "3_3") (pintype "unspecified"))
      (node (ref "IC6") (pin "4") (pinfunction "C3_4") (pintype "unspecified"))
    )
    (net (code "118") (name "Net-(IC6-C4)") (class "Default")
      (node (ref "CON4") (pin "5") (pinfunction "5_5") (pintype "unspecified"))
      (node (ref "IC6") (pin "5") (pinfunction "C4_5") (pintype "unspecified"))
    )
    (net (code "119") (name "Net-(IC6-C5)") (class "Default")
      (node (ref "CON5") (pin "16") (pinfunction "16_16") (pintype "unspecified"))
      (node (ref "IC6") (pin "6") (pinfunction "C5_6") (pintype "unspecified"))
    )
    (net (code "120") (name "Net-(IC6-C6)") (class "Default")
      (node (ref "CON5") (pin "14") (pinfunction "14_14") (pintype "unspecified"))
      (node (ref "IC6") (pin "7") (pinfunction "C6_7") (pintype "unspecified"))
    )
    (net (code "121") (name "Net-(IC6-C7)") (class "Default")
      (node (ref "CON5") (pin "12") (pinfunction "12_12") (pintype "unspecified"))
      (node (ref "IC6") (pin "8") (pinfunction "C7_8") (pintype "unspecified"))
    )
    (net (code "122") (name "Net-(IC6-C8)") (class "Default")
      (node (ref "CON5") (pin "10") (pinfunction "10_10") (pintype "unspecified"))
      (node (ref "IC6") (pin "9") (pinfunction "C8_9") (pintype "unspecified"))
    )
    (net (code "123") (name "Net-(IC6-C9)") (class "Default")
      (node (ref "CON5") (pin "8") (pinfunction "8_8") (pintype "unspecified"))
      (node (ref "IC6") (pin "10") (pinfunction "C9_10") (pintype "unspecified"))
    )
    (net (code "124") (name "Net-(IC6-C10)") (class "Default")
      (node (ref "CON5") (pin "6") (pinfunction "6_6") (pintype "unspecified"))
      (node (ref "IC6") (pin "11") (pinfunction "C10_11") (pintype "unspecified"))
    )
    (net (code "125") (name "Net-(IC6-C11)") (class "Default")
      (node (ref "CON5") (pin "4") (pinfunction "4_4") (pintype "unspecified"))
      (node (ref "IC6") (pin "12") (pinfunction "C11_12") (pintype "unspecified"))
    )
    (net (code "126") (name "Net-(IC6-C12)") (class "Default")
      (node (ref "CON5") (pin "2") (pinfunction "2_2") (pintype "unspecified"))
      (node (ref "IC6") (pin "13") (pinfunction "C12_13") (pintype "unspecified"))
    )
    (net (code "127") (name "Net-(IC6-C13)") (class "Default")
      (node (ref "CON5") (pin "3") (pinfunction "3_3") (pintype "unspecified"))
      (node (ref "IC6") (pin "14") (pinfunction "C13_14") (pintype "unspecified"))
    )
    (net (code "128") (name "Net-(IC6-C14)") (class "Default")
      (node (ref "CON5") (pin "5") (pinfunction "5_5") (pintype "unspecified"))
      (node (ref "IC6") (pin "15") (pinfunction "C14_15") (pintype "unspecified"))
    )
    (net (code "129") (name "Net-(IC6-C15)") (class "Default")
      (node (ref "CON5") (pin "7") (pinfunction "7_7") (pintype "unspecified"))
      (node (ref "IC6") (pin "16") (pinfunction "C15_16") (pintype "unspecified"))
    )
    (net (code "130") (name "Net-(IC6-EN)") (class "Default")
      (node (ref "IC6") (pin "19") (pinfunction "EN_19") (pintype "unspecified"))
      (node (ref "R1") (pin "1") (pinfunction "1_1") (pintype "unspecified"))
    )
    (net (code "131") (name "Net-(IC7-C0)") (class "Default")
      (node (ref "CON3") (pin "12") (pinfunction "12_12") (pintype "unspecified"))
      (node (ref "IC7") (pin "1") (pinfunction "C0_1") (pintype "unspecified"))
    )
    (net (code "132") (name "Net-(IC7-C1)") (class "Default")
      (node (ref "CON3") (pin "10") (pinfunction "10_10") (pintype "unspecified"))
      (node (ref "IC7") (pin "2") (pinfunction "C1_2") (pintype "unspecified"))
    )
    (net (code "133") (name "Net-(IC7-C2)") (class "Default")
      (node (ref "CON3") (pin "8") (pinfunction "8_8") (pintype "unspecified"))
      (node (ref "IC7") (pin "3") (pinfunction "C2_3") (pintype "unspecified"))
    )
    (net (code "134") (name "Net-(IC7-C3)") (class "Default")
      (node (ref "CON3") (pin "6") (pinfunction "6_6") (pintype "unspecified"))
      (node (ref "IC7") (pin "4") (pinfunction "C3_4") (pintype "unspecified"))
    )
    (net (code "135") (name "Net-(IC7-C4)") (class "Default")
      (node (ref "CON3") (pin "4") (pinfunction "4_4") (pintype "unspecified"))
      (node (ref "IC7") (pin "5") (pinfunction "C4_5") (pintype "unspecified"))
    )
    (net (code "136") (name "Net-(IC7-C5)") (class "Default")
      (node (ref "CON3") (pin "2") (pinfunction "2_2") (pintype "unspecified"))
      (node (ref "IC7") (pin "6") (pinfunction "C5_6") (pintype "unspecified"))
    )
    (net (code "137") (name "Net-(IC7-C6)") (class "Default")
      (node (ref "CON3") (pin "1") (pinfunction "1_1") (pintype "unspecified"))
      (node (ref "IC7") (pin "7") (pinfunction "C6_7") (pintype "unspecified"))
    )
    (net (code "138") (name "Net-(IC7-C7)") (class "Default")
      (node (ref "CON3") (pin "3") (pinfunction "3_3") (pintype "unspecified"))
      (node (ref "IC7") (pin "8") (pinfunction "C7_8") (pintype "unspecified"))
    )
    (net (code "139") (name "Net-(IC7-C8)") (class "Default")
      (node (ref "CON3") (pin "5") (pinfunction "5_5") (pintype "unspecified"))
      (node (ref "IC7") (pin "9") (pinfunction "C8_9") (pintype "unspecified"))
    )
    (net (code "140") (name "Net-(IC7-C9)") (class "Default")
      (node (ref "CON3") (pin "7") (pinfunction "7_7") (pintype "unspecified"))
      (node (ref "IC7") (pin "10") (pinfunction "C9_10") (pintype "unspecified"))
    )
    (net (code "141") (name "Net-(IC7-C10)") (class "Default")
      (node (ref "CON3") (pin "9") (pinfunction "9_9") (pintype "unspecified"))
      (node (ref "IC7") (pin "11") (pinfunction "C10_11") (pintype "unspecified"))
    )
    (net (code "142") (name "Net-(IC7-C11)") (class "Default")
      (node (ref "CON3") (pin "11") (pinfunction "11_11") (pintype "unspecified"))
      (node (ref "IC7") (pin "12") (pinfunction "C11_12") (pintype "unspecified"))
    )
    (net (code "143") (name "Net-(IC7-C12)") (class "Default")
      (node (ref "CON4") (pin "12") (pinfunction "12_12") (pintype "unspecified"))
      (node (ref "IC7") (pin "13") (pinfunction "C12_13") (pintype "unspecified"))
    )
    (net (code "144") (name "Net-(IC7-C13)") (class "Default")
      (node (ref "CON4") (pin "10") (pinfunction "10_10") (pintype "unspecified"))
      (node (ref "IC7") (pin "14") (pinfunction "C13_14") (pintype "unspecified"))
    )
    (net (code "145") (name "Net-(IC7-C14)") (class "Default")
      (node (ref "CON4") (pin "8") (pinfunction "8_8") (pintype "unspecified"))
      (node (ref "IC7") (pin "15") (pinfunction "C14_15") (pintype "unspecified"))
    )
    (net (code "146") (name "Net-(IC7-C15)") (class "Default")
      (node (ref "CON4") (pin "6") (pinfunction "6_6") (pintype "unspecified"))
      (node (ref "IC7") (pin "16") (pinfunction "C15_16") (pintype "unspecified"))
    )
    (net (code "147") (name "Net-(IC7-EN)") (class "Default")
      (node (ref "IC7") (pin "19") (pinfunction "EN_19") (pintype "unspecified"))
      (node (ref "R2") (pin "2") (pinfunction "2_2") (pintype "unspecified"))
    )
    (net (code "148") (name "unconnected-(CON28-Pad2)") (class "Default")
      (node (ref "CON28") (pin "2") (pinfunction "2_2") (pintype "unspecified"))
    )
    (net (code "149") (name "unconnected-(CON28-Pad3)") (class "Default")
      (node (ref "CON28") (pin "3") (pinfunction "3_3") (pintype "unspecified"))
    )
    (net (code "150") (name "unconnected-(CON28-Pad4)") (class "Default")
      (node (ref "CON28") (pin "4") (pinfunction "4_4") (pintype "unspecified"))
    )
    (net (code "151") (name "unconnected-(CON29-Pad2)") (class "Default")
      (node (ref "CON29") (pin "2") (pinfunction "2_2") (pintype "unspecified"))
    )
    (net (code "152") (name "unconnected-(CON29-Pad3)") (class "Default")
      (node (ref "CON29") (pin "3") (pinfunction "3_3") (pintype "unspecified"))
    )
    (net (code "153") (name "unconnected-(CON29-Pad4)") (class "Default")
      (node (ref "CON29") (pin "4") (pinfunction "4_4") (pintype "unspecified"))
    )
    (net (code "154") (name "unconnected-(IC1-3.3V-Pad79)") (class "Default")
      (node (ref "IC1") (pin "79") (pinfunction "3.3V_79") (pintype "unspecified"))
    )
    (net (code "155") (name "unconnected-(IC1-3.3V-Pad80)") (class "Default")
      (node (ref "IC1") (pin "80") (pinfunction "3.3V_80") (pintype "unspecified"))
    )
    (net (code "156") (name "unconnected-(IC1-AREF-Pad78)") (class "Default")
      (node (ref "IC1") (pin "78") (pinfunction "AREF_78") (pintype "unspecified"))
    )
    (net (code "157") (name "unconnected-(IC1-MISO-Pad40)") (class "Default")
      (node (ref "IC1") (pin "40") (pinfunction "MISO_40") (pintype "unspecified"))
    )
    (net (code "158") (name "unconnected-(IC1-MOSI-Pad41)") (class "Default")
      (node (ref "IC1") (pin "41") (pinfunction "MOSI_41") (pintype "unspecified"))
    )
    (net (code "159") (name "unconnected-(IC1-RX-Pad76)") (class "Default")
      (node (ref "IC1") (pin "76") (pinfunction "RX_76") (pintype "unspecified"))
    )
    (net (code "160") (name "unconnected-(IC1-Reset-Pad44)") (class "Default")
      (node (ref "IC1") (pin "44") (pinfunction "Reset_44") (pintype "unspecified"))
    )
    (net (code "161") (name "unconnected-(IC1-Reset-Pad77)") (class "Default")
      (node (ref "IC1") (pin "77") (pinfunction "Reset_77") (pintype "unspecified"))
    )
    (net (code "162") (name "unconnected-(IC1-SCK-Pad42)") (class "Default")
      (node (ref "IC1") (pin "42") (pinfunction "SCK_42") (pintype "unspecified"))
    )
    (net (code "163") (name "unconnected-(IC1-TX-Pad75)") (class "Default")
      (node (ref "IC1") (pin "75") (pinfunction "TX_75") (pintype "unspecified"))
    )
    (net (code "164") (name "unconnected-(IC1-VIN-Pad85)") (class "Default")
      (node (ref "IC1") (pin "85") (pinfunction "VIN_85") (pintype "unspecified"))
    )
    (net (code "165") (name "unconnected-(IC1-VIN-Pad86)") (class "Default")
      (node (ref "IC1") (pin "86") (pinfunction "VIN_86") (pintype "unspecified"))
    )
    (net (code "166") (name "unconnected-(IC2-QF-Pad5)") (class "Default")
      (node (ref "IC2") (pin "5") (pinfunction "QF_5") (pintype "unspecified"))
    )
    (net (code "167") (name "unconnected-(IC2-QG-Pad6)") (class "Default")
      (node (ref "IC2") (pin "6") (pinfunction "QG_6") (pintype "unspecified"))
    )
    (net (code "168") (name "unconnected-(IC2-QH-Pad7)") (class "Default")
      (node (ref "IC2") (pin "7") (pinfunction "QH_7") (pintype "unspecified"))
    )
    (net (code "169") (name "unconnected-(IC2-QH-Pad9)") (class "Default")
      (node (ref "IC2") (pin "9") (pinfunction "QH_9") (pintype "output"))
    )
  )
)
